# Sheet1.net
KiCad netlist of a schematic drawn in Altium Designer
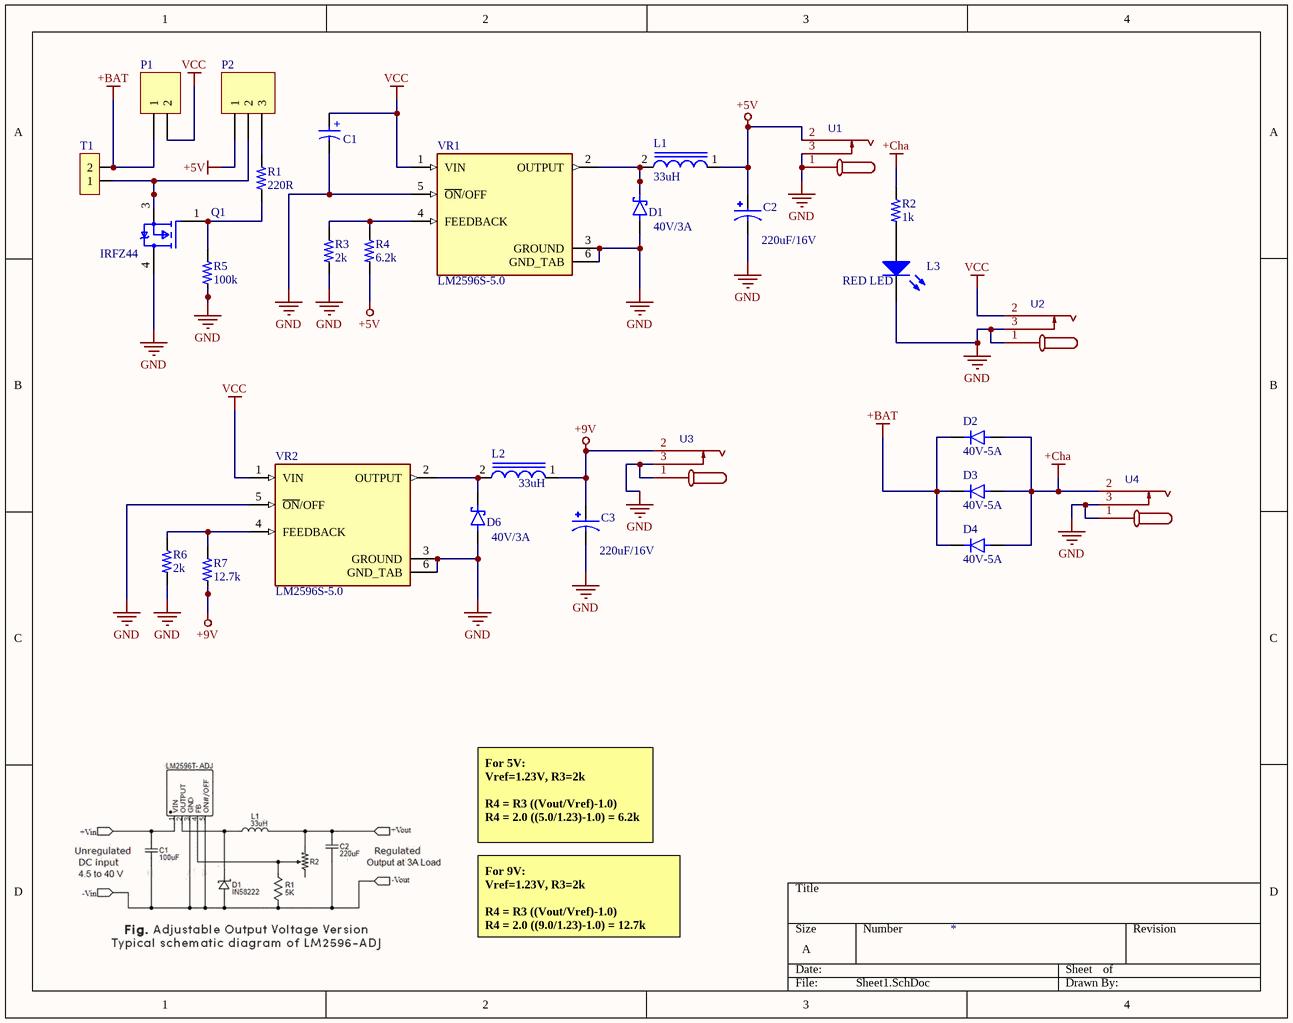
[diagram p0: Sheet1.SchDoc]

(export (version "E")
  (design (tool "Eeschema 10.0.6"))
  (components
    (comp (ref "C1")
      (value "4.7µF")
      (footprint "WCAP-PSLP_D6.3H7.7")
      (description "470uF 16V 230mA@120Hz ±20% SMD,D6.3xL7.7mm Aluminum Electrolytic Capacitors - SMD ROHS")
      (fields (field (name "MANUFACTURER") "JIERR") (field (name "MFR. PART #") "JVJ16V470M6x8"))
      (libsource (lib "Altium LibraryHub-main") (part "CAP ALUM 470uF ±20% 16V SMD"))
    )
    (comp (ref "C2")
      (value "220uF/16V")
      (footprint "CAP-220")
      (description "220uF 16V 110mA@120Hz ±20% SMD,D6.3xL7.7mm Aluminum Electrolytic Capacitors - SMD ROHS")
      (fields (field (name "MANUFACTURER") "KNSCHA") (field (name "MFR. PART #") "RVT220UF16V67RV0015"))
      (libsource (lib "Altium LibraryHub-main") (part "CAP ALUM 220uF ±20% 16V SMD"))
    )
    (comp (ref "C3")
      (value "220uF/16V")
      (footprint "CAP-220")
      (description "220uF 16V 110mA@120Hz ±20% SMD,D6.3xL7.7mm Aluminum Electrolytic Capacitors - SMD ROHS")
      (fields (field (name "MANUFACTURER") "KNSCHA") (field (name "MFR. PART #") "RVT220UF16V67RV0015"))
      (libsource (lib "Altium LibraryHub-main") (part "CAP ALUM 220uF ±20% 16V SMD"))
    )
    (comp (ref "D1")
      (value "40V/3A")
      (footprint "SOD-123")
      (description "40V Independent 550mV@3A 3A SMA(DO-214AC) Schottky Diodes ROHS")
      (fields (field (name "MANUFACTURER") "GOODWORK") (field (name "MFR. PART #") "SS34"))
      (libsource (lib "Altium LibraryHub-main") (part "DIODE SCHOTTKY 40V SMA(DO-214AC)"))
    )
    (comp (ref "D2")
      (value "40V-5A")
      (footprint "DIODE-214AC")
      (description "40V 700mV@5A 5A SMA Schottky Diodes ROHS")
      (fields (field (name "MANUFACTURER") "SMA(DO-214AC)") (field (name "MFR. PART #") "SS54"))
      (libsource (lib "Altium LibraryHub-main") (part "DIODE SCHOTTKY 40V SMA"))
    )
    (comp (ref "D3")
      (value "40V-5A")
      (footprint "DIODE-214AC")
      (description "40V 700mV@5A 5A SMA Schottky Diodes ROHS")
      (fields (field (name "MANUFACTURER") "SMA(DO-214AC)") (field (name "MFR. PART #") "SS54"))
      (libsource (lib "Altium LibraryHub-main") (part "DIODE SCHOTTKY 40V SMA"))
    )
    (comp (ref "D4")
      (value "40V-5A")
      (footprint "DIODE-214AC")
      (description "40V 700mV@5A 5A SMA Schottky Diodes ROHS")
      (fields (field (name "MANUFACTURER") "SMA(DO-214AC)") (field (name "MFR. PART #") "SS54"))
      (libsource (lib "Altium LibraryHub-main") (part "DIODE SCHOTTKY 40V SMA"))
    )
    (comp (ref "D6")
      (value "40V/3A")
      (footprint "SOD-123")
      (description "40V Independent 550mV@3A 3A SMA(DO-214AC) Schottky Diodes ROHS")
      (fields (field (name "MANUFACTURER") "GOODWORK") (field (name "MFR. PART #") "SS34"))
      (libsource (lib "Altium LibraryHub-main") (part "DIODE SCHOTTKY 40V SMA(DO-214AC)"))
    )
    (comp (ref "L1")
      (value "33uH")
      (footprint "INDP125125X600N")
      (description "3A 33uH Magnetic Shielded Inductor ±20% SMD,12x12mm Power Inductors ROHS")
      (fields (field (name "MANUFACTURER") "YJYCOIN") (field (name "MFR. PART #") "YPRH1207-330M"))
      (libsource (lib "Altium LibraryHub-main") (part "FIXED IND 33uH 3A 65m SMD,12x12mm"))
    )
    (comp (ref "L2")
      (value "33uH")
      (footprint "INDP125125X600N")
      (description "3A 33uH Magnetic Shielded Inductor ±20% SMD,12x12mm Power Inductors ROHS")
      (fields (field (name "MANUFACTURER") "YJYCOIN") (field (name "MFR. PART #") "YPRH1207-330M"))
      (libsource (lib "Altium LibraryHub-main") (part "FIXED IND 33uH 3A 65m SMD,12x12mm"))
    )
    (comp (ref "L3")
      (value "RED LED")
      (footprint "LED_5mm_G")
      (fields
        (field (name "MANUFACTURER") "XINGLIGHT")
        (field (name "MFR. PART #") "Re-released for DXP Platform.")
        (field (name "LCSC PART #") "Altium Limited")
      )
      (libsource (lib "Altium LibraryHub-main") (part "LED RED RED LENS TH"))
    )
    (comp (ref "P1")
      (value "Header 2")
      (footprint "My_1X02")
      (description "Header, 2-Pin")
      (fields (field (name "ASID PART NUMBER") "Header 2-AS"))
      (libsource (lib "Altium LibraryHub-main") (part "Header 2"))
    )
    (comp (ref "P2")
      (value "Header 3")
      (footprint "My_1X03")
      (description "Header, 3-Pin")
      (fields (field (name "ASID PART NUMBER") "Header 3-AS"))
      (libsource (lib "Altium LibraryHub-main") (part "Header 3"))
    )
    (comp (ref "Q1")
      (value "IRFZ44")
      (footprint "TO-263")
      (description "60V 60A 12mΩ@10V,25A 87W 3V 1 N-Channel TO-263 MOSFETs ROHS")
      (fields (field (name "MANUFACTURER") "Minos") (field (name "MFR. PART #") "IRFZ44NS"))
      (libsource (lib "Altium LibraryHub-main") (part "MOSFET N-CH 60V 60A TO-263 SMD"))
    )
    (comp (ref "R1")
      (value "220R")
      (footprint "RES_0805")
      (description "125mW Thick Film Resistor 150V ±100ppm/℃ ±5% 220Ω 0805 Chip Resistor - Surface Mount ROHS")
      (fields (field (name "MANUFACTURER") "FOJAN") (field (name "MFR. PART #") "FRC0805J221 TS"))
      (libsource (lib "Altium LibraryHub-main") (part "RES 220 ±5% 125mW 0805"))
    )
    (comp (ref "R2")
      (value "1k")
      (footprint "RES_0805")
      (description "125mW Thick Film Resistor 150V ±100ppm/℃ ±5% 1kΩ 0805 Chip Resistor - Surface Mount ROHS")
      (fields (field (name "MANUFACTURER") "UNI-ROYAL") (field (name "MFR. PART #") "0805W8J0102T5E"))
      (libsource (lib "Altium LibraryHub-main") (part "RES 1K 125mW 0805"))
    )
    (comp (ref "R3")
      (value "2k")
      (footprint "RES_0805")
      (description "125mW Thick Film Resistor 150V ±100ppm/℃ ±1% 2kΩ 0805 Chip Resistor - Surface Mount ROHS")
      (fields (field (name "MANUFACTURER") "YAGEO") (field (name "MFR. PART #") "RC0805FR-072KL"))
      (libsource (lib "Altium LibraryHub-main") (part "RES 2K 125mW 0805"))
    )
    (comp (ref "R4")
      (value "6.2k")
      (footprint "RES_0805")
      (description "125mW Thick Film Resistor 150V ±100ppm/℃ ±1% 6.2kΩ 0805 Chip Resistor - Surface Mount ROHS")
      (fields (field (name "MANUFACTURER") "YAGEO") (field (name "MFR. PART #") "RC0805FR-076K2L"))
      (libsource (lib "Altium LibraryHub-main") (part "RES 6.2K 125mW 0805"))
    )
    (comp (ref "R5")
      (value "100k")
      (footprint "RES_0805")
      (description "125mW Thick Film Resistor 150V ±100ppm/℃ ±5% 100kΩ 0805 Chip Resistor - Surface Mount ROHS")
      (fields (field (name "MANUFACTURER") "FOJAN") (field (name "MFR. PART #") "FRC0805J104 TS"))
      (libsource (lib "Altium LibraryHub-main") (part "RES 100k ±5% 125mW 0805"))
    )
    (comp (ref "R6")
      (value "2k")
      (footprint "RES_0805")
      (description "125mW Thick Film Resistor 150V ±100ppm/℃ ±1% 2kΩ 0805 Chip Resistor - Surface Mount ROHS")
      (fields (field (name "MANUFACTURER") "YAGEO") (field (name "MFR. PART #") "RC0805FR-072KL"))
      (libsource (lib "Altium LibraryHub-main") (part "RES 2K 125mW 0805"))
    )
    (comp (ref "R7")
      (value "12.7k")
      (footprint "RES_0805")
      (description "125mW Thick Film Resistor ±100ppm/℃ ±1% 12.7kΩ 0805 Chip Resistor - Surface Mount ROHS")
      (fields (field (name "MANUFACTURER") "YAGEO") (field (name "MFR. PART #") "RC0805FR-1312K7L"))
      (libsource (lib "Altium LibraryHub-main") (part "RES 12.7K 125mW 0805"))
    )
    (comp (ref "T1")
      (value "Terminal")
      (footprint "KF301 2Pin")
      (fields
        (field (name "MANUFACTURER") "KANGNEX")
        (field (name "MFR. PART #") "WJ301V-5.0-2P")
        (field (name "LCSC PART #") "C8475")
      )
      (libsource (lib "Altium LibraryHub-main") (part "TERM BLK 2POS 5mm TH"))
    )
    (comp (ref "U1")
      (value "DC-062A-4A-2.0")
      (footprint "Plugin")
      (fields (field (name "MANUFACTURER") "XKB Connection") (field (name "LCSC PART #") "C5147479"))
      (libsource (lib "Altium LibraryHub-main") (part "DC-062A-4A-2.0"))
    )
    (comp (ref "U2")
      (value "DC-062A-4A-2.0")
      (footprint "Plugin")
      (fields (field (name "MANUFACTURER") "XKB Connection") (field (name "LCSC PART #") "C5147479"))
      (libsource (lib "Altium LibraryHub-main") (part "DC-062A-4A-2.0"))
    )
    (comp (ref "U3")
      (value "DC-062A-4A-2.0")
      (footprint "Plugin")
      (fields (field (name "MANUFACTURER") "XKB Connection") (field (name "LCSC PART #") "C5147479"))
      (libsource (lib "Altium LibraryHub-main") (part "DC-062A-4A-2.0"))
    )
    (comp (ref "U4")
      (value "DC-062A-4A-2.0")
      (footprint "Plugin")
      (fields (field (name "MANUFACTURER") "XKB Connection") (field (name "LCSC PART #") "C5147479"))
      (libsource (lib "Altium LibraryHub-main") (part "DC-062A-4A-2.0"))
    )
    (comp (ref "VR1")
      (value "LM2596S-5.0")
      (footprint "TO-263-5")
      (description "Buck Fixed 7V~40V 5V 3A TO-263-5 DC-DC Converters ROHS")
      (fields (field (name "MANUFACTURER") "UMW") (field (name "MFR. PART #") "LM2596S-5.0(UMW)"))
      (libsource (lib "Altium LibraryHub-main") (part "LM2596S-5.0"))
    )
    (comp (ref "VR2")
      (value "LM2596S-5.0")
      (footprint "TO-263-5")
      (description "Buck Fixed 7V~40V 5V 3A TO-263-5 DC-DC Converters ROHS")
      (fields (field (name "MANUFACTURER") "UMW") (field (name "MFR. PART #") "LM2596S-5.0(UMW)"))
      (libsource (lib "Altium LibraryHub-main") (part "LM2596S-5.0"))
    )
  )
  (nets
    (net (code "1") (name "+5V") (class "Default")
      (node (ref "C2") (pin "1") (pinfunction "1_1") (pintype "passive"))
      (node (ref "L1") (pin "1") (pinfunction "1_1") (pintype "passive"))
      (node (ref "P2") (pin "1") (pinfunction "1_1") (pintype "passive"))
      (node (ref "R4") (pin "1") (pinfunction "1_1") (pintype "passive"))
      (node (ref "U1") (pin "2") (pinfunction "2_2") (pintype "passive"))
    )
    (net (code "2") (name "+9V") (class "Default")
      (node (ref "C3") (pin "1") (pinfunction "1_1") (pintype "passive"))
      (node (ref "L2") (pin "1") (pinfunction "1_1") (pintype "passive"))
      (node (ref "R7") (pin "1") (pinfunction "1_1") (pintype "passive"))
      (node (ref "U3") (pin "2") (pinfunction "2_2") (pintype "passive"))
    )
    (net (code "3") (name "+BAT") (class "Default")
      (node (ref "D2") (pin "C") (pinfunction "K_C") (pintype "passive"))
      (node (ref "D3") (pin "C") (pinfunction "K_C") (pintype "passive"))
      (node (ref "D4") (pin "C") (pinfunction "K_C") (pintype "passive"))
      (node (ref "P1") (pin "1") (pinfunction "1_1") (pintype "passive"))
      (node (ref "T1") (pin "2") (pinfunction "2_2") (pintype "passive"))
    )
    (net (code "4") (name "+Cha") (class "Default")
      (node (ref "D2") (pin "A") (pinfunction "A_A") (pintype "passive"))
      (node (ref "D3") (pin "A") (pinfunction "A_A") (pintype "passive"))
      (node (ref "D4") (pin "A") (pinfunction "A_A") (pintype "passive"))
      (node (ref "R2") (pin "2") (pinfunction "2_2") (pintype "passive"))
      (node (ref "U4") (pin "2") (pinfunction "2_2") (pintype "passive"))
    )
    (net (code "5") (name "GND") (class "Default")
      (node (ref "C1") (pin "2") (pinfunction "N_2") (pintype "passive"))
      (node (ref "C2") (pin "2") (pinfunction "2_2") (pintype "passive"))
      (node (ref "C3") (pin "2") (pinfunction "2_2") (pintype "passive"))
      (node (ref "D1") (pin "A") (pinfunction "A_A") (pintype "passive"))
      (node (ref "D6") (pin "A") (pinfunction "A_A") (pintype "passive"))
      (node (ref "L3") (pin "K") (pinfunction "K_K") (pintype "passive"))
      (node (ref "Q1") (pin "4") (pinfunction "D_4") (pintype "passive"))
      (node (ref "R3") (pin "1") (pinfunction "1_1") (pintype "passive"))
      (node (ref "R5") (pin "1") (pinfunction "1_1") (pintype "passive"))
      (node (ref "R6") (pin "1") (pinfunction "1_1") (pintype "passive"))
      (node (ref "U1") (pin "1") (pinfunction "1_1") (pintype "passive"))
      (node (ref "U1") (pin "3") (pinfunction "3_3") (pintype "passive"))
      (node (ref "U2") (pin "1") (pinfunction "1_1") (pintype "passive"))
      (node (ref "U2") (pin "3") (pinfunction "3_3") (pintype "passive"))
      (node (ref "U3") (pin "1") (pinfunction "1_1") (pintype "passive"))
      (node (ref "U3") (pin "3") (pinfunction "3_3") (pintype "passive"))
      (node (ref "U4") (pin "1") (pinfunction "1_1") (pintype "passive"))
      (node (ref "U4") (pin "3") (pinfunction "3_3") (pintype "passive"))
      (node (ref "VR1") (pin "3") (pinfunction "GROUND_3") (pintype "power_in"))
      (node (ref "VR1") (pin "5") (pinfunction "~{ON}/OFF_5") (pintype "input"))
      (node (ref "VR1") (pin "6") (pinfunction "GND_TAB_6") (pintype "power_in"))
      (node (ref "VR2") (pin "3") (pinfunction "GROUND_3") (pintype "power_in"))
      (node (ref "VR2") (pin "5") (pinfunction "~{ON}/OFF_5") (pintype "input"))
      (node (ref "VR2") (pin "6") (pinfunction "GND_TAB_6") (pintype "power_in"))
    )
    (net (code "6") (name "Net-(L3-PadA)") (class "Default")
      (node (ref "L3") (pin "A") (pinfunction "A_A") (pintype "passive"))
      (node (ref "R2") (pin "1") (pinfunction "1_1") (pintype "passive"))
    )
    (net (code "7") (name "Net-(P2-Pad3)") (class "Default")
      (node (ref "P2") (pin "3") (pinfunction "3_3") (pintype "passive"))
      (node (ref "R1") (pin "2") (pinfunction "2_2") (pintype "passive"))
    )
    (net (code "8") (name "Net-(Q1-G)") (class "Default")
      (node (ref "Q1") (pin "1") (pinfunction "G_1") (pintype "passive"))
      (node (ref "R1") (pin "1") (pinfunction "1_1") (pintype "passive"))
      (node (ref "R5") (pin "2") (pinfunction "2_2") (pintype "passive"))
    )
    (net (code "9") (name "Net-(Q1-S)") (class "Default")
      (node (ref "P2") (pin "2") (pinfunction "2_2") (pintype "passive"))
      (node (ref "Q1") (pin "3") (pinfunction "S_3") (pintype "passive"))
      (node (ref "T1") (pin "1") (pinfunction "1_1") (pintype "passive"))
    )
    (net (code "10") (name "Net-(VR1-FEEDBACK)") (class "Default")
      (node (ref "R3") (pin "2") (pinfunction "2_2") (pintype "passive"))
      (node (ref "R4") (pin "2") (pinfunction "2_2") (pintype "passive"))
      (node (ref "VR1") (pin "4") (pinfunction "FEEDBACK_4") (pintype "input"))
    )
    (net (code "11") (name "Net-(VR1-OUTPUT)") (class "Default")
      (node (ref "D1") (pin "K") (pinfunction "K_K") (pintype "passive"))
      (node (ref "L1") (pin "2") (pinfunction "2_2") (pintype "passive"))
      (node (ref "VR1") (pin "2") (pinfunction "OUTPUT_2") (pintype "output"))
    )
    (net (code "12") (name "Net-(VR2-FEEDBACK)") (class "Default")
      (node (ref "R6") (pin "2") (pinfunction "2_2") (pintype "passive"))
      (node (ref "R7") (pin "2") (pinfunction "2_2") (pintype "passive"))
      (node (ref "VR2") (pin "4") (pinfunction "FEEDBACK_4") (pintype "input"))
    )
    (net (code "13") (name "Net-(VR2-OUTPUT)") (class "Default")
      (node (ref "D6") (pin "K") (pinfunction "K_K") (pintype "passive"))
      (node (ref "L2") (pin "2") (pinfunction "2_2") (pintype "passive"))
      (node (ref "VR2") (pin "2") (pinfunction "OUTPUT_2") (pintype "output"))
    )
    (net (code "14") (name "VCC") (class "Default")
      (node (ref "C1") (pin "1") (pinfunction "P_1") (pintype "passive"))
      (node (ref "P1") (pin "2") (pinfunction "2_2") (pintype "passive"))
      (node (ref "U2") (pin "2") (pinfunction "2_2") (pintype "passive"))
      (node (ref "VR1") (pin "1") (pinfunction "VIN_1") (pintype "input"))
      (node (ref "VR2") (pin "1") (pinfunction "VIN_1") (pintype "input"))
    )
  )
)
